# Schematic_v1_1.net
KiCad netlist of a schematic drawn in EAGLE
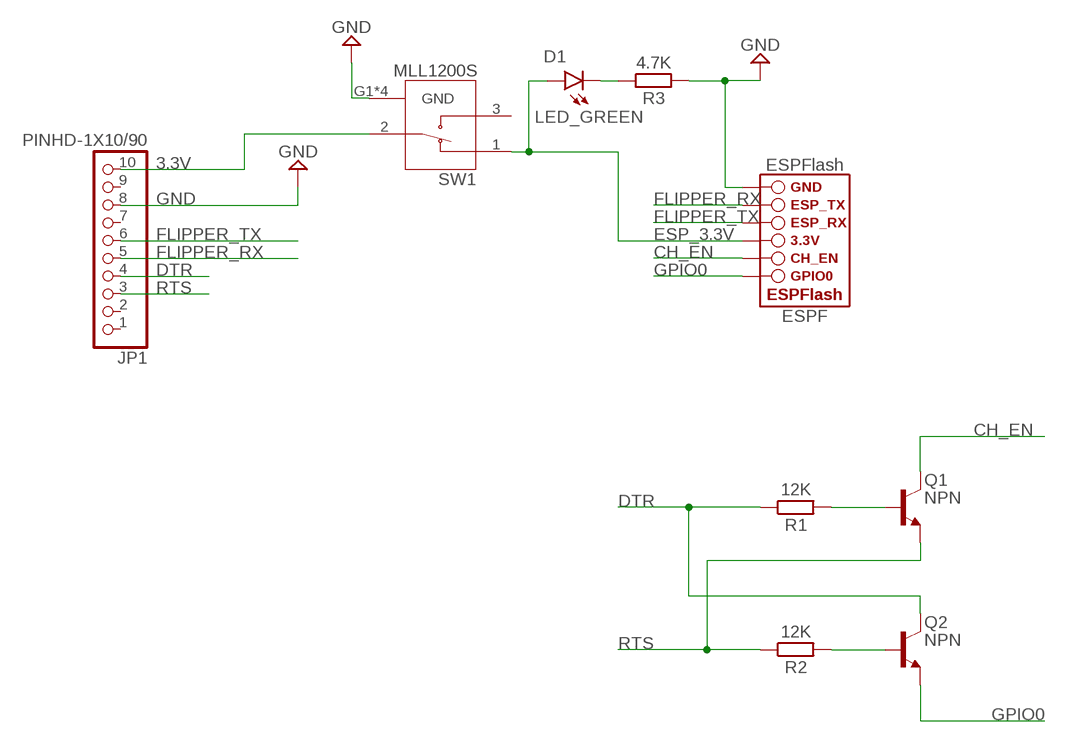
[diagram p0: schematic, sheet 1]

(export (version "E")
  (design (tool "Eeschema 10.0.6"))
  (components
    (comp (ref "D1")
      (value "LED_GREEN")
      (footprint "eagle-import:LEDC1608X55N_FLAT-B")
      (libsource (lib "eagle-import") (part "CHIP-FLAT-B_0603-0.55MM"))
    )
    (comp (ref "ESPF")
      (value "ESPFLASH-1X6-2.54-PLAIN")
      (footprint "eagle-import:1X6-2.54-PLAIN")
      (libsource (lib "eagle-import") (part "ESPFLASH-1X6-2.54-PLAIN"))
    )
    (comp (ref "JP1")
      (value "PINHD-1X10/90")
      (footprint "eagle-import:1X10_90")
      (libsource (lib "eagle-import") (part "PINHD-1X10/90"))
    )
    (comp (ref "Q1")
      (value "NPN")
      (footprint "eagle-import:SOT95P237X112-3N")
      (libsource (lib "eagle-import") (part "NPNSOT23-BEC_"))
    )
    (comp (ref "Q2")
      (value "NPN")
      (footprint "eagle-import:SOT95P237X112-3N")
      (libsource (lib "eagle-import") (part "NPNSOT23-BEC_"))
    )
    (comp (ref "R1")
      (value "12K")
      (footprint "eagle-import:RESC1608X60")
      (libsource (lib "eagle-import") (part "RCHIP-0603(1608-METRIC)_"))
    )
    (comp (ref "R2")
      (value "12K")
      (footprint "eagle-import:RESC1608X60")
      (libsource (lib "eagle-import") (part "RCHIP-0603(1608-METRIC)_"))
    )
    (comp (ref "R3")
      (value "4.7K")
      (footprint "eagle-import:RESC1608X60")
      (libsource (lib "eagle-import") (part "RCHIP-0603(1608-METRIC)_"))
    )
    (comp (ref "SW1")
      (value "MLL1200S")
      (footprint "eagle-import:SW_MLL1200S")
      (fields (field (name "COMMENT") "1437575-1"))
      (libsource (lib "eagle-import") (part "MLL1200S"))
    )
  )
  (nets
    (net (code "1") (name "/3.3V") (class "Default")
      (node (ref "JP1") (pin "10") (pinfunction "10_10") (pintype "passive"))
      (node (ref "SW1") (pin "2") (pinfunction "2_2") (pintype "passive"))
    )
    (net (code "2") (name "/CH_EN") (class "Default")
      (node (ref "ESPF") (pin "5") (pinfunction "CH_EN_5") (pintype "passive"))
      (node (ref "Q1") (pin "3") (pinfunction "C_3") (pintype "passive"))
    )
    (net (code "3") (name "/DTR") (class "Default")
      (node (ref "JP1") (pin "4") (pinfunction "4_4") (pintype "passive"))
      (node (ref "Q2") (pin "3") (pinfunction "C_3") (pintype "passive"))
      (node (ref "R1") (pin "1") (pinfunction "1_1") (pintype "passive"))
    )
    (net (code "4") (name "/ESP_3.3V") (class "Default")
      (node (ref "D1") (pin "A") (pinfunction "A_A") (pintype "passive"))
      (node (ref "ESPF") (pin "4") (pinfunction "3.3V_4") (pintype "passive"))
      (node (ref "SW1") (pin "1") (pinfunction "1_1") (pintype "passive"))
    )
    (net (code "5") (name "/FLIPPER_RX") (class "Default")
      (node (ref "ESPF") (pin "2") (pinfunction "ESP_TX_2") (pintype "passive"))
      (node (ref "JP1") (pin "5") (pinfunction "5_5") (pintype "passive"))
    )
    (net (code "6") (name "/FLIPPER_TX") (class "Default")
      (node (ref "ESPF") (pin "3") (pinfunction "ESP_RX_3") (pintype "passive"))
      (node (ref "JP1") (pin "6") (pinfunction "6_6") (pintype "passive"))
    )
    (net (code "7") (name "/GPIO0") (class "Default")
      (node (ref "ESPF") (pin "6") (pinfunction "GPIO0_6") (pintype "passive"))
      (node (ref "Q2") (pin "2") (pinfunction "E_2") (pintype "passive"))
    )
    (net (code "8") (name "/RTS") (class "Default")
      (node (ref "JP1") (pin "3") (pinfunction "3_3") (pintype "passive"))
      (node (ref "Q1") (pin "2") (pinfunction "E_2") (pintype "passive"))
      (node (ref "R2") (pin "1") (pinfunction "1_1") (pintype "passive"))
    )
    (net (code "9") (name "GND") (class "Default")
      (node (ref "ESPF") (pin "1") (pinfunction "GND_1") (pintype "passive"))
      (node (ref "JP1") (pin "8") (pinfunction "8_8") (pintype "passive"))
      (node (ref "R3") (pin "2") (pinfunction "2_2") (pintype "passive"))
      (node (ref "SW1") (pin "G1") (pinfunction "GND_G1") (pintype "power_in"))
      (node (ref "SW1") (pin "G2") (pinfunction "GND_G2") (pintype "power_in"))
      (node (ref "SW1") (pin "G3") (pinfunction "GND_G3") (pintype "power_in"))
      (node (ref "SW1") (pin "G4") (pinfunction "GND_G4") (pintype "power_in"))
    )
    (net (code "10") (name "Net-(D1-PadC)") (class "Default")
      (node (ref "D1") (pin "C") (pinfunction "C_C") (pintype "passive"))
      (node (ref "R3") (pin "1") (pinfunction "1_1") (pintype "passive"))
    )
    (net (code "11") (name "Net-(Q1-B)") (class "Default")
      (node (ref "Q1") (pin "1") (pinfunction "B_1") (pintype "passive"))
      (node (ref "R1") (pin "2") (pinfunction "2_2") (pintype "passive"))
    )
    (net (code "12") (name "Net-(Q2-B)") (class "Default")
      (node (ref "Q2") (pin "1") (pinfunction "B_1") (pintype "passive"))
      (node (ref "R2") (pin "2") (pinfunction "2_2") (pintype "passive"))
    )
    (net (code "13") (name "unconnected-(JP1-Pad1)") (class "Default")
      (node (ref "JP1") (pin "1") (pinfunction "1_1") (pintype "passive"))
    )
    (net (code "14") (name "unconnected-(JP1-Pad2)") (class "Default")
      (node (ref "JP1") (pin "2") (pinfunction "2_2") (pintype "passive"))
    )
    (net (code "15") (name "unconnected-(JP1-Pad7)") (class "Default")
      (node (ref "JP1") (pin "7") (pinfunction "7_7") (pintype "passive"))
    )
    (net (code "16") (name "unconnected-(JP1-Pad9)") (class "Default")
      (node (ref "JP1") (pin "9") (pinfunction "9_9") (pintype "passive"))
    )
    (net (code "17") (name "unconnected-(SW1-Pad3)") (class "Default")
      (node (ref "SW1") (pin "3") (pinfunction "3_3") (pintype "passive"))
    )
  )
)
